# Driver.net
KiCad netlist of a schematic drawn in EAGLE
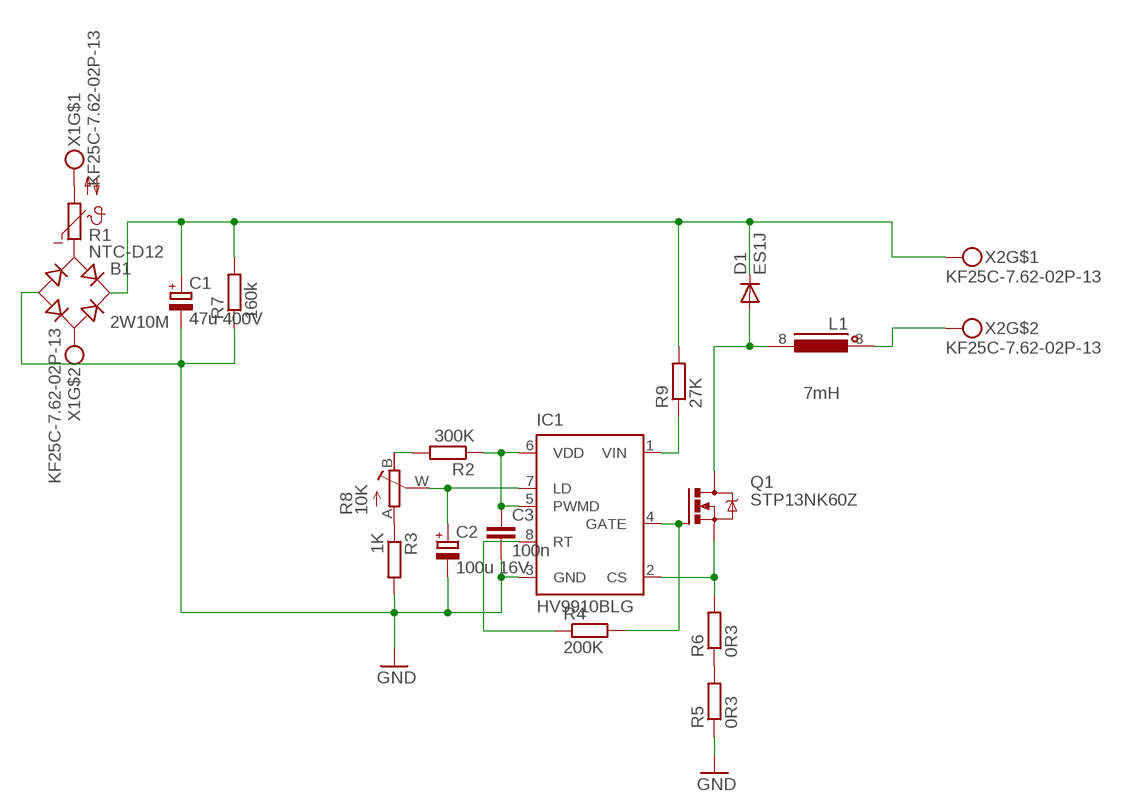
[diagram p0: schematic, sheet 1]

(export (version "E")
  (design (tool "Eeschema 10.0.6"))
  (components
    (comp (ref "B1")
      (value "2W10M")
      (footprint "eagle-import:RB1A")
      (libsource (lib "eagle-import") (part "RB1A"))
    )
    (comp (ref "C1")
      (value "47u 400V")
      (footprint "eagle-import:E7,5-16-32-HORIZ")
      (libsource (lib "eagle-import") (part "CPOL-EUE7,5-16-32-H"))
    )
    (comp (ref "C2")
      (value "100u 16V")
      (footprint "eagle-import:E2,5-6")
      (libsource (lib "eagle-import") (part "CPOL-EUE2.5-6"))
    )
    (comp (ref "C3")
      (value "100n")
      (footprint "eagle-import:C0805")
      (libsource (lib "eagle-import") (part "C-EUC0805"))
    )
    (comp (ref "D1")
      (value "ES1J")
      (footprint "eagle-import:DO214AC")
      (libsource (lib "eagle-import") (part "DIODE-DO214AC"))
    )
    (comp (ref "IC1")
      (value "HV9910BLG")
      (footprint "eagle-import:SOIC-08LG")
      (fields (field (name "MPN") "MXHV9910B"))
      (libsource (lib "eagle-import") (part "HV9910BLG"))
    )
    (comp (ref "L1")
      (value "INDUCTOREE20V")
      (footprint "eagle-import:EE20_10PIN")
      (libsource (lib "eagle-import") (part "INDUCTOREE20V"))
    )
    (comp (ref "Q1")
      (value "STP13NK60Z")
      (footprint "eagle-import:TO220BV")
      (libsource (lib "eagle-import") (part "IRF740"))
    )
    (comp (ref "R1")
      (value "NTC-D12")
      (footprint "eagle-import:NTC-D12")
      (libsource (lib "eagle-import") (part "NTC-D12"))
    )
    (comp (ref "R2")
      (value "300K")
      (footprint "eagle-import:R0805")
      (libsource (lib "eagle-import") (part "R-EU_R0805"))
    )
    (comp (ref "R3")
      (value "1K")
      (footprint "eagle-import:R0805")
      (libsource (lib "eagle-import") (part "R-EU_R0805"))
    )
    (comp (ref "R4")
      (value "200K")
      (footprint "eagle-import:R0805")
      (libsource (lib "eagle-import") (part "R-EU_R0805"))
    )
    (comp (ref "R5")
      (value "0R3")
      (footprint "eagle-import:0414_15")
      (libsource (lib "eagle-import") (part "R-EU_0414/15"))
    )
    (comp (ref "R6")
      (value "0R3")
      (footprint "eagle-import:0414_15")
      (libsource (lib "eagle-import") (part "R-EU_0414/15"))
    )
    (comp (ref "R7")
      (value "160k")
      (footprint "eagle-import:0204_7")
      (libsource (lib "eagle-import") (part "R-EU_0204/7"))
    )
    (comp (ref "R8")
      (value "10K")
      (footprint "eagle-import:RJ9W")
      (libsource (lib "eagle-import") (part "R_POTTURN-X"))
    )
    (comp (ref "R9")
      (value "27K")
      (footprint "eagle-import:P0613_15")
      (libsource (lib "eagle-import") (part "R-EU_0613/15"))
    )
    (comp (ref "X1")
      (value "KF25C-7.62-02P-13")
      (footprint "eagle-import:KF25C-7.62-02P-13")
      (libsource (lib "eagle-import") (part "KF25C-7.62-02P-13"))
    )
    (comp (ref "X2")
      (value "KF25C-7.62-02P-13")
      (footprint "eagle-import:KF25C-7.62-02P-13")
      (libsource (lib "eagle-import") (part "KF25C-7.62-02P-13"))
    )
  )
  (nets
    (net (code "1") (name "GND") (class "Default")
      (node (ref "B1") (pin "-") (pinfunction "-_-") (pintype "passive"))
      (node (ref "C1") (pin "-") (pinfunction "-_-") (pintype "passive"))
      (node (ref "C2") (pin "-") (pinfunction "-_-") (pintype "passive"))
      (node (ref "C3") (pin "2") (pinfunction "2_2") (pintype "passive"))
      (node (ref "IC1") (pin "3") (pinfunction "GND_3") (pintype "power_in"))
      (node (ref "R3") (pin "2") (pinfunction "2_2") (pintype "passive"))
      (node (ref "R5") (pin "1") (pinfunction "1_1") (pintype "passive"))
      (node (ref "R7") (pin "1") (pinfunction "1_1") (pintype "passive"))
    )
    (net (code "2") (name "Net-(B1-PadAC1)") (class "Default")
      (node (ref "B1") (pin "AC1") (pinfunction "AC1_AC1") (pintype "passive"))
      (node (ref "R1") (pin "1") (pinfunction "1_1") (pintype "passive"))
    )
    (net (code "3") (name "Net-(IC1-CS)") (class "Default")
      (node (ref "IC1") (pin "2") (pinfunction "CS_2") (pintype "input"))
      (node (ref "Q1") (pin "S") (pinfunction "S_S") (pintype "passive"))
      (node (ref "R6") (pin "2") (pinfunction "2_2") (pintype "passive"))
    )
    (net (code "4") (name "Net-(IC1-GATE)") (class "Default")
      (node (ref "IC1") (pin "4") (pinfunction "GATE_4") (pintype "output"))
      (node (ref "Q1") (pin "G") (pinfunction "G_G") (pintype "passive"))
      (node (ref "R4") (pin "2") (pinfunction "2_2") (pintype "passive"))
    )
    (net (code "5") (name "Net-(IC1-LD)") (class "Default")
      (node (ref "C2") (pin "+") (pinfunction "+_+") (pintype "passive"))
      (node (ref "IC1") (pin "7") (pinfunction "LD_7") (pintype "input"))
      (node (ref "R8") (pin "W") (pinfunction "S_W") (pintype "passive"))
    )
    (net (code "6") (name "Net-(IC1-PWMD)") (class "Default")
      (node (ref "C3") (pin "1") (pinfunction "1_1") (pintype "passive"))
      (node (ref "IC1") (pin "5") (pinfunction "PWMD_5") (pintype "input"))
      (node (ref "IC1") (pin "6") (pinfunction "VDD_6") (pintype "power_in"))
      (node (ref "R2") (pin "1") (pinfunction "1_1") (pintype "passive"))
    )
    (net (code "7") (name "Net-(IC1-RT)") (class "Default")
      (node (ref "IC1") (pin "8") (pinfunction "RT_8") (pintype "passive"))
      (node (ref "R4") (pin "1") (pinfunction "1_1") (pintype "passive"))
    )
    (net (code "8") (name "Net-(IC1-VIN)") (class "Default")
      (node (ref "IC1") (pin "1") (pinfunction "VIN_1") (pintype "input"))
      (node (ref "R9") (pin "1") (pinfunction "1_1") (pintype "passive"))
    )
    (net (code "9") (name "Net-(L1-1)") (class "Default")
      (node (ref "L1") (pin "3") (pinfunction "1_3") (pintype "passive"))
      (node (ref "X2") (pin "P$2") (pinfunction "KL_P$2") (pintype "passive"))
    )
    (net (code "10") (name "Net-(L1-2)") (class "Default")
      (node (ref "D1") (pin "A") (pinfunction "A_A") (pintype "passive"))
      (node (ref "L1") (pin "8") (pinfunction "2_8") (pintype "passive"))
      (node (ref "Q1") (pin "D") (pinfunction "D_D") (pintype "passive"))
    )
    (net (code "11") (name "Net-(R3-Pad1)") (class "Default")
      (node (ref "R3") (pin "1") (pinfunction "1_1") (pintype "passive"))
      (node (ref "R8") (pin "A") (pinfunction "A_A") (pintype "passive"))
    )
    (net (code "12") (name "Net-(R5-Pad2)") (class "Default")
      (node (ref "R5") (pin "2") (pinfunction "2_2") (pintype "passive"))
      (node (ref "R6") (pin "1") (pinfunction "1_1") (pintype "passive"))
    )
    (net (code "13") (name "Net-(R8-E)") (class "Default")
      (node (ref "R2") (pin "2") (pinfunction "2_2") (pintype "passive"))
      (node (ref "R8") (pin "B") (pinfunction "E_B") (pintype "passive"))
    )
    (net (code "14") (name "Net-(X1A-KL)") (class "Default")
      (node (ref "R1") (pin "2") (pinfunction "2_2") (pintype "passive"))
      (node (ref "X1") (pin "P$1") (pinfunction "KL_P$1") (pintype "passive"))
    )
    (net (code "15") (name "Net-(X1B-KL)") (class "Default")
      (node (ref "B1") (pin "AC2") (pinfunction "AC2_AC2") (pintype "passive"))
      (node (ref "X1") (pin "P$2") (pinfunction "KL_P$2") (pintype "passive"))
    )
    (net (code "16") (name "Net-(X2A-KL)") (class "Default")
      (node (ref "B1") (pin "+") (pinfunction "+_+") (pintype "passive"))
      (node (ref "C1") (pin "+") (pinfunction "+_+") (pintype "passive"))
      (node (ref "D1") (pin "C") (pinfunction "C_C") (pintype "passive"))
      (node (ref "R7") (pin "2") (pinfunction "2_2") (pintype "passive"))
      (node (ref "R9") (pin "2") (pinfunction "2_2") (pintype "passive"))
      (node (ref "X2") (pin "P$1") (pinfunction "KL_P$1") (pintype "passive"))
    )
  )
)
